# sqm-gps.net
KiCad netlist of a schematic drawn in EAGLE
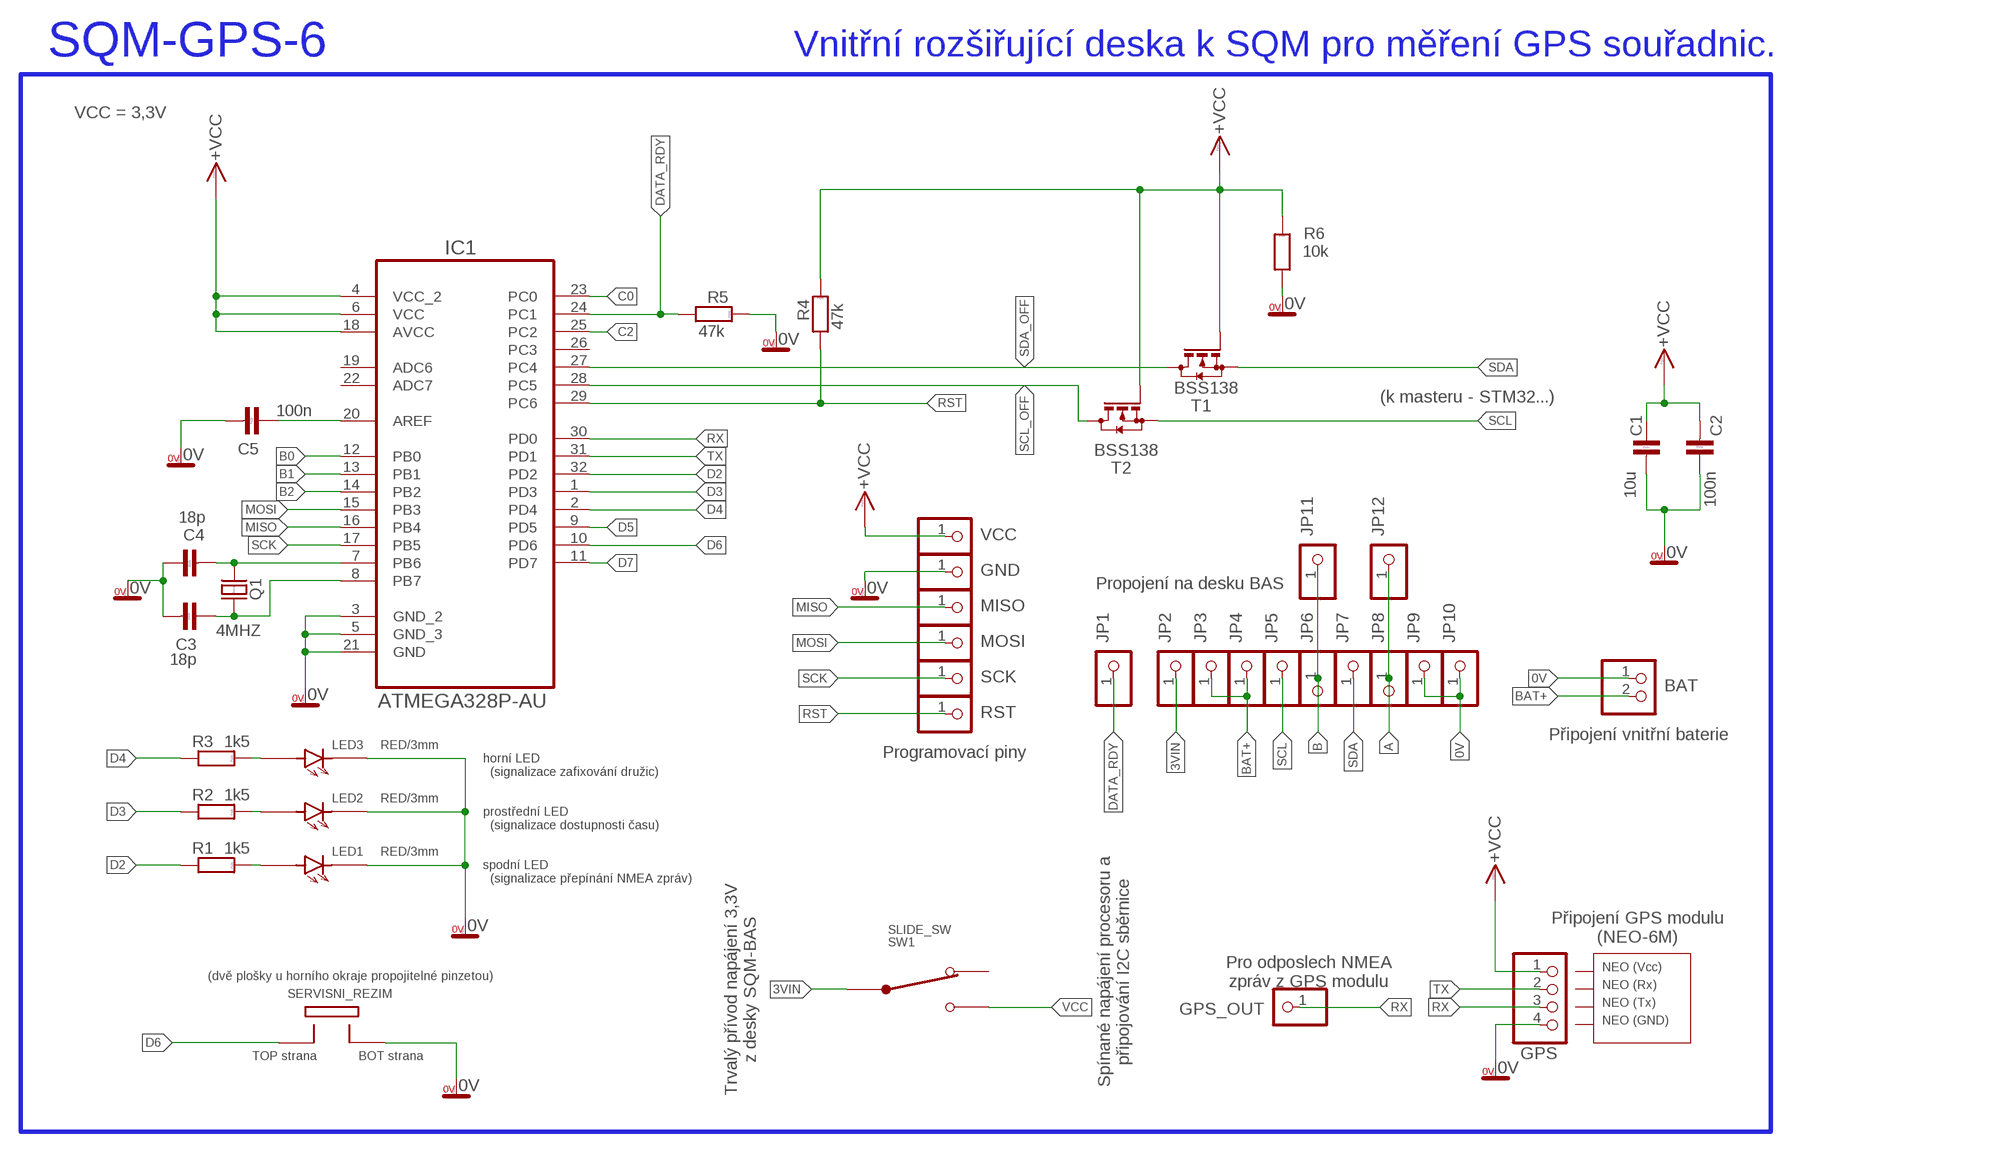
[diagram p0: schematic, sheet 1]

(export (version "E")
  (design (tool "Eeschema 10.0.6"))
  (components
    (comp (ref "BAT")
      (value "PINHD-1X2")
      (footprint "eagle-import:1X02")
      (libsource (lib "eagle-import") (part "PINHD-1X2"))
    )
    (comp (ref "C1")
      (value "10u")
      (footprint "eagle-import:1206")
      (libsource (lib "eagle-import") (part "C-KERAMIK_SMD_1206"))
    )
    (comp (ref "C2")
      (value "100n")
      (footprint "eagle-import:0805")
      (libsource (lib "eagle-import") (part "C-KERAMIK_SMD_0805"))
    )
    (comp (ref "C3")
      (value "18p")
      (footprint "eagle-import:0805")
      (libsource (lib "eagle-import") (part "C-KERAMIK_SMD_0805"))
    )
    (comp (ref "C4")
      (value "18p")
      (footprint "eagle-import:0805")
      (libsource (lib "eagle-import") (part "C-KERAMIK_SMD_0805"))
    )
    (comp (ref "C5")
      (value "100n")
      (footprint "eagle-import:0805")
      (libsource (lib "eagle-import") (part "C-KERAMIK_SMD_0805"))
    )
    (comp (ref "GND")
      (value "PINHD-1X1")
      (footprint "eagle-import:1X01")
      (libsource (lib "eagle-import") (part "PINHD-1X1"))
    )
    (comp (ref "GPS")
      (value "PINHD-1X4")
      (footprint "eagle-import:1X04")
      (libsource (lib "eagle-import") (part "PINHD-1X4"))
    )
    (comp (ref "GPS_OUT")
      (value "PINHD-1X1")
      (footprint "eagle-import:1X01")
      (libsource (lib "eagle-import") (part "PINHD-1X1"))
    )
    (comp (ref "IC1")
      (value "ATMEGA328P-AU")
      (footprint "eagle-import:QFP80P900X900X120-32N")
      (libsource (lib "eagle-import") (part "ATMEGA328P-AU"))
    )
    (comp (ref "JP1")
      (value "PINHD-1X1")
      (footprint "eagle-import:1X01")
      (libsource (lib "eagle-import") (part "PINHD-1X1"))
    )
    (comp (ref "JP2")
      (value "PINHD-1X1")
      (footprint "eagle-import:1X01")
      (libsource (lib "eagle-import") (part "PINHD-1X1"))
    )
    (comp (ref "JP3")
      (value "PINHD-1X1")
      (footprint "eagle-import:1X01")
      (libsource (lib "eagle-import") (part "PINHD-1X1"))
    )
    (comp (ref "JP4")
      (value "PINHD-1X1")
      (footprint "eagle-import:1X01")
      (libsource (lib "eagle-import") (part "PINHD-1X1"))
    )
    (comp (ref "JP5")
      (value "PINHD-1X1")
      (footprint "eagle-import:1X01")
      (libsource (lib "eagle-import") (part "PINHD-1X1"))
    )
    (comp (ref "JP6")
      (value "PINHD-1X1")
      (footprint "eagle-import:1X01")
      (libsource (lib "eagle-import") (part "PINHD-1X1"))
    )
    (comp (ref "JP7")
      (value "PINHD-1X1")
      (footprint "eagle-import:1X01")
      (libsource (lib "eagle-import") (part "PINHD-1X1"))
    )
    (comp (ref "JP8")
      (value "PINHD-1X1")
      (footprint "eagle-import:1X01")
      (libsource (lib "eagle-import") (part "PINHD-1X1"))
    )
    (comp (ref "JP9")
      (value "PINHD-1X1")
      (footprint "eagle-import:1X01")
      (libsource (lib "eagle-import") (part "PINHD-1X1"))
    )
    (comp (ref "JP10")
      (value "PINHD-1X1")
      (footprint "eagle-import:1X01")
      (libsource (lib "eagle-import") (part "PINHD-1X1"))
    )
    (comp (ref "JP11")
      (value "PINHD-1X1")
      (footprint "eagle-import:1X01")
      (libsource (lib "eagle-import") (part "PINHD-1X1"))
    )
    (comp (ref "JP12")
      (value "PINHD-1X1")
      (footprint "eagle-import:1X01")
      (libsource (lib "eagle-import") (part "PINHD-1X1"))
    )
    (comp (ref "LED1")
      (value "RED/3mm")
      (footprint "eagle-import:LED3MM_BOK")
      (libsource (lib "eagle-import") (part "LED3MM_BOK"))
    )
    (comp (ref "LED2")
      (value "RED/3mm")
      (footprint "eagle-import:LED3MM_BOK")
      (libsource (lib "eagle-import") (part "LED3MM_BOK"))
    )
    (comp (ref "LED3")
      (value "RED/3mm")
      (footprint "eagle-import:LED3MM_BOK")
      (libsource (lib "eagle-import") (part "LED3MM_BOK"))
    )
    (comp (ref "MISO")
      (value "PINHD-1X1")
      (footprint "eagle-import:1X01")
      (libsource (lib "eagle-import") (part "PINHD-1X1"))
    )
    (comp (ref "MOSI")
      (value "PINHD-1X1")
      (footprint "eagle-import:1X01")
      (libsource (lib "eagle-import") (part "PINHD-1X1"))
    )
    (comp (ref "Q1")
      (value "4MHZ")
      (footprint "eagle-import:HC-49U")
      (libsource (lib "eagle-import") (part "Q_HC-49U"))
    )
    (comp (ref "R1")
      (value "1k5")
      (footprint "eagle-import:0805")
      (libsource (lib "eagle-import") (part "R_SMD_0805"))
    )
    (comp (ref "R2")
      (value "1k5")
      (footprint "eagle-import:0805")
      (libsource (lib "eagle-import") (part "R_SMD_0805"))
    )
    (comp (ref "R3")
      (value "1k5")
      (footprint "eagle-import:0805")
      (libsource (lib "eagle-import") (part "R_SMD_0805"))
    )
    (comp (ref "R4")
      (value "47k")
      (footprint "eagle-import:0805")
      (libsource (lib "eagle-import") (part "R_SMD_0805"))
    )
    (comp (ref "R5")
      (value "47k")
      (footprint "eagle-import:0805")
      (libsource (lib "eagle-import") (part "R_SMD_0805"))
    )
    (comp (ref "R6")
      (value "10k")
      (footprint "eagle-import:0805")
      (libsource (lib "eagle-import") (part "R_SMD_0805"))
    )
    (comp (ref "RST")
      (value "PINHD-1X1")
      (footprint "eagle-import:1X01")
      (libsource (lib "eagle-import") (part "PINHD-1X1"))
    )
    (comp (ref "SCK")
      (value "PINHD-1X1")
      (footprint "eagle-import:1X01")
      (libsource (lib "eagle-import") (part "PINHD-1X1"))
    )
    (comp (ref "SERVISNI_REZIM")
      (value "TOP_BOT_PIN")
      (footprint "eagle-import:TOP_BOT_PIN")
      (libsource (lib "eagle-import") (part "TOP_BOT_PIN"))
    )
    (comp (ref "SW1")
      (value "SLIDE_SW")
      (footprint "eagle-import:SLIDE_SW")
      (libsource (lib "eagle-import") (part "SLIDE_SW"))
    )
    (comp (ref "T1")
      (value "BSS138")
      (footprint "eagle-import:SOT23")
      (libsource (lib "eagle-import") (part "BSS123"))
    )
    (comp (ref "T2")
      (value "BSS138")
      (footprint "eagle-import:SOT23")
      (libsource (lib "eagle-import") (part "BSS123"))
    )
    (comp (ref "VCC")
      (value "PINHD-1X1")
      (footprint "eagle-import:1X01")
      (libsource (lib "eagle-import") (part "PINHD-1X1"))
    )
  )
  (nets
    (net (code "1") (name "0V") (class "Default")
      (node (ref "BAT") (pin "1") (pinfunction "1_1") (pintype "passive"))
      (node (ref "C1") (pin "2") (pinfunction "2_2") (pintype "passive"))
      (node (ref "C2") (pin "1") (pinfunction "1_1") (pintype "passive"))
      (node (ref "C3") (pin "2") (pinfunction "2_2") (pintype "passive"))
      (node (ref "C4") (pin "1") (pinfunction "1_1") (pintype "passive"))
      (node (ref "C5") (pin "2") (pinfunction "2_2") (pintype "passive"))
      (node (ref "GND") (pin "1") (pinfunction "1_1") (pintype "passive"))
      (node (ref "GPS") (pin "4") (pinfunction "4_4") (pintype "passive"))
      (node (ref "IC1") (pin "21") (pinfunction "GND_21") (pintype "passive"))
      (node (ref "IC1") (pin "3") (pinfunction "GND_2_3") (pintype "passive"))
      (node (ref "IC1") (pin "5") (pinfunction "GND_3_5") (pintype "passive"))
      (node (ref "JP10") (pin "1") (pinfunction "1_1") (pintype "passive"))
      (node (ref "JP9") (pin "1") (pinfunction "1_1") (pintype "passive"))
      (node (ref "LED1") (pin "K") (pinfunction "K_K") (pintype "bidirectional"))
      (node (ref "LED2") (pin "K") (pinfunction "K_K") (pintype "bidirectional"))
      (node (ref "LED3") (pin "K") (pinfunction "K_K") (pintype "bidirectional"))
      (node (ref "R5") (pin "2") (pinfunction "2_2") (pintype "passive"))
      (node (ref "R6") (pin "1") (pinfunction "1_1") (pintype "passive"))
      (node (ref "SERVISNI_REZIM") (pin "P2") (pinfunction "P2_P2") (pintype "bidirectional"))
    )
    (net (code "2") (name "3VIN") (class "Default")
      (node (ref "JP2") (pin "1") (pinfunction "1_1") (pintype "passive"))
      (node (ref "SW1") (pin "PIN_COM") (pinfunction "PIN_COM_PIN_COM") (pintype "bidirectional"))
    )
    (net (code "3") (name "A") (class "Default")
      (node (ref "JP12") (pin "1") (pinfunction "1_1") (pintype "passive"))
      (node (ref "JP8") (pin "1") (pinfunction "1_1") (pintype "passive"))
    )
    (net (code "4") (name "B") (class "Default")
      (node (ref "JP11") (pin "1") (pinfunction "1_1") (pintype "passive"))
      (node (ref "JP6") (pin "1") (pinfunction "1_1") (pintype "passive"))
    )
    (net (code "5") (name "B0") (class "Default")
      (node (ref "IC1") (pin "12") (pinfunction "PB0_12") (pintype "bidirectional"))
    )
    (net (code "6") (name "B1") (class "Default")
      (node (ref "IC1") (pin "13") (pinfunction "PB1_13") (pintype "bidirectional"))
    )
    (net (code "7") (name "B2") (class "Default")
      (node (ref "IC1") (pin "14") (pinfunction "PB2_14") (pintype "bidirectional"))
    )
    (net (code "8") (name "BAT+") (class "Default")
      (node (ref "BAT") (pin "2") (pinfunction "2_2") (pintype "passive"))
      (node (ref "JP3") (pin "1") (pinfunction "1_1") (pintype "passive"))
      (node (ref "JP4") (pin "1") (pinfunction "1_1") (pintype "passive"))
    )
    (net (code "9") (name "C0") (class "Default")
      (node (ref "IC1") (pin "23") (pinfunction "PC0_23") (pintype "bidirectional"))
    )
    (net (code "10") (name "C2") (class "Default")
      (node (ref "IC1") (pin "25") (pinfunction "PC2_25") (pintype "bidirectional"))
    )
    (net (code "11") (name "D2") (class "Default")
      (node (ref "IC1") (pin "32") (pinfunction "PD2_32") (pintype "bidirectional"))
      (node (ref "R1") (pin "1") (pinfunction "1_1") (pintype "passive"))
    )
    (net (code "12") (name "D3") (class "Default")
      (node (ref "IC1") (pin "1") (pinfunction "PD3_1") (pintype "bidirectional"))
      (node (ref "R2") (pin "1") (pinfunction "1_1") (pintype "passive"))
    )
    (net (code "13") (name "D4") (class "Default")
      (node (ref "IC1") (pin "2") (pinfunction "PD4_2") (pintype "bidirectional"))
      (node (ref "R3") (pin "1") (pinfunction "1_1") (pintype "passive"))
    )
    (net (code "14") (name "D5") (class "Default")
      (node (ref "IC1") (pin "9") (pinfunction "PD5_9") (pintype "bidirectional"))
    )
    (net (code "15") (name "D6") (class "Default")
      (node (ref "IC1") (pin "10") (pinfunction "PD6_10") (pintype "bidirectional"))
      (node (ref "SERVISNI_REZIM") (pin "P1") (pinfunction "P1_P1") (pintype "bidirectional"))
    )
    (net (code "16") (name "D7") (class "Default")
      (node (ref "IC1") (pin "11") (pinfunction "PD7_11") (pintype "bidirectional"))
    )
    (net (code "17") (name "DATA_RDY") (class "Default")
      (node (ref "IC1") (pin "24") (pinfunction "PC1_24") (pintype "bidirectional"))
      (node (ref "JP1") (pin "1") (pinfunction "1_1") (pintype "passive"))
      (node (ref "R5") (pin "1") (pinfunction "1_1") (pintype "passive"))
    )
    (net (code "18") (name "MISO") (class "Default")
      (node (ref "IC1") (pin "16") (pinfunction "PB4_16") (pintype "bidirectional"))
      (node (ref "MISO") (pin "1") (pinfunction "1_1") (pintype "passive"))
    )
    (net (code "19") (name "MOSI") (class "Default")
      (node (ref "IC1") (pin "15") (pinfunction "PB3_15") (pintype "bidirectional"))
      (node (ref "MOSI") (pin "1") (pinfunction "1_1") (pintype "passive"))
    )
    (net (code "20") (name "Net-(IC1-AREF)") (class "Default")
      (node (ref "C5") (pin "1") (pinfunction "1_1") (pintype "passive"))
      (node (ref "IC1") (pin "20") (pinfunction "AREF_20") (pintype "input"))
    )
    (net (code "21") (name "Net-(IC1-PB6)") (class "Default")
      (node (ref "C4") (pin "2") (pinfunction "2_2") (pintype "passive"))
      (node (ref "IC1") (pin "7") (pinfunction "PB6_7") (pintype "bidirectional"))
      (node (ref "Q1") (pin "2") (pinfunction "2_2") (pintype "passive"))
    )
    (net (code "22") (name "Net-(IC1-PB7)") (class "Default")
      (node (ref "C3") (pin "1") (pinfunction "1_1") (pintype "passive"))
      (node (ref "IC1") (pin "8") (pinfunction "PB7_8") (pintype "bidirectional"))
      (node (ref "Q1") (pin "1") (pinfunction "1_1") (pintype "passive"))
    )
    (net (code "23") (name "Net-(LED1-PadA)") (class "Default")
      (node (ref "LED1") (pin "A") (pinfunction "A_A") (pintype "bidirectional"))
      (node (ref "R1") (pin "2") (pinfunction "2_2") (pintype "passive"))
    )
    (net (code "24") (name "Net-(LED2-PadA)") (class "Default")
      (node (ref "LED2") (pin "A") (pinfunction "A_A") (pintype "bidirectional"))
      (node (ref "R2") (pin "2") (pinfunction "2_2") (pintype "passive"))
    )
    (net (code "25") (name "Net-(LED3-PadA)") (class "Default")
      (node (ref "LED3") (pin "A") (pinfunction "A_A") (pintype "bidirectional"))
      (node (ref "R3") (pin "2") (pinfunction "2_2") (pintype "passive"))
    )
    (net (code "26") (name "RST") (class "Default")
      (node (ref "IC1") (pin "29") (pinfunction "PC6_29") (pintype "bidirectional"))
      (node (ref "R4") (pin "1") (pinfunction "1_1") (pintype "passive"))
      (node (ref "RST") (pin "1") (pinfunction "1_1") (pintype "passive"))
    )
    (net (code "27") (name "RX") (class "Default")
      (node (ref "GPS") (pin "3") (pinfunction "3_3") (pintype "passive"))
      (node (ref "GPS_OUT") (pin "1") (pinfunction "1_1") (pintype "passive"))
      (node (ref "IC1") (pin "30") (pinfunction "PD0_30") (pintype "bidirectional"))
    )
    (net (code "28") (name "SCK") (class "Default")
      (node (ref "IC1") (pin "17") (pinfunction "PB5_17") (pintype "bidirectional"))
      (node (ref "SCK") (pin "1") (pinfunction "1_1") (pintype "passive"))
    )
    (net (code "29") (name "SCL") (class "Default")
      (node (ref "JP5") (pin "1") (pinfunction "1_1") (pintype "passive"))
      (node (ref "T2") (pin "2") (pinfunction "S_2") (pintype "passive"))
    )
    (net (code "30") (name "SCL_OFF") (class "Default")
      (node (ref "IC1") (pin "28") (pinfunction "PC5_28") (pintype "bidirectional"))
      (node (ref "T2") (pin "3") (pinfunction "D_3") (pintype "passive"))
    )
    (net (code "31") (name "SDA") (class "Default")
      (node (ref "JP7") (pin "1") (pinfunction "1_1") (pintype "passive"))
      (node (ref "T1") (pin "2") (pinfunction "S_2") (pintype "passive"))
    )
    (net (code "32") (name "SDA_OFF") (class "Default")
      (node (ref "IC1") (pin "27") (pinfunction "PC4_27") (pintype "bidirectional"))
      (node (ref "T1") (pin "3") (pinfunction "D_3") (pintype "passive"))
    )
    (net (code "33") (name "TX") (class "Default")
      (node (ref "GPS") (pin "2") (pinfunction "2_2") (pintype "passive"))
      (node (ref "IC1") (pin "31") (pinfunction "PD1_31") (pintype "bidirectional"))
    )
    (net (code "34") (name "VCC") (class "Default")
      (node (ref "C1") (pin "1") (pinfunction "1_1") (pintype "passive"))
      (node (ref "C2") (pin "2") (pinfunction "2_2") (pintype "passive"))
      (node (ref "GPS") (pin "1") (pinfunction "1_1") (pintype "passive"))
      (node (ref "IC1") (pin "18") (pinfunction "AVCC_18") (pintype "power_in"))
      (node (ref "IC1") (pin "4") (pinfunction "VCC_2_4") (pintype "power_in"))
      (node (ref "IC1") (pin "6") (pinfunction "VCC_6") (pintype "power_in"))
      (node (ref "R4") (pin "2") (pinfunction "2_2") (pintype "passive"))
      (node (ref "R6") (pin "2") (pinfunction "2_2") (pintype "passive"))
      (node (ref "SW1") (pin "PIN_2") (pinfunction "PIN_2_PIN_2") (pintype "bidirectional"))
      (node (ref "T1") (pin "1") (pinfunction "G_1") (pintype "passive"))
      (node (ref "T2") (pin "1") (pinfunction "G_1") (pintype "passive"))
      (node (ref "VCC") (pin "1") (pinfunction "1_1") (pintype "passive"))
    )
    (net (code "35") (name "unconnected-(IC1-ADC6-Pad19)") (class "Default")
      (node (ref "IC1") (pin "19") (pinfunction "ADC6_19") (pintype "input"))
    )
    (net (code "36") (name "unconnected-(IC1-ADC7-Pad22)") (class "Default")
      (node (ref "IC1") (pin "22") (pinfunction "ADC7_22") (pintype "input"))
    )
    (net (code "37") (name "unconnected-(IC1-PC3-Pad26)") (class "Default")
      (node (ref "IC1") (pin "26") (pinfunction "PC3_26") (pintype "bidirectional"))
    )
    (net (code "38") (name "unconnected-(SW1-PadPIN_1)") (class "Default")
      (node (ref "SW1") (pin "PIN_1") (pinfunction "PIN_1_PIN_1") (pintype "bidirectional"))
    )
  )
)
